# led2.net
KiCad netlist of a schematic drawn in Altium Designer
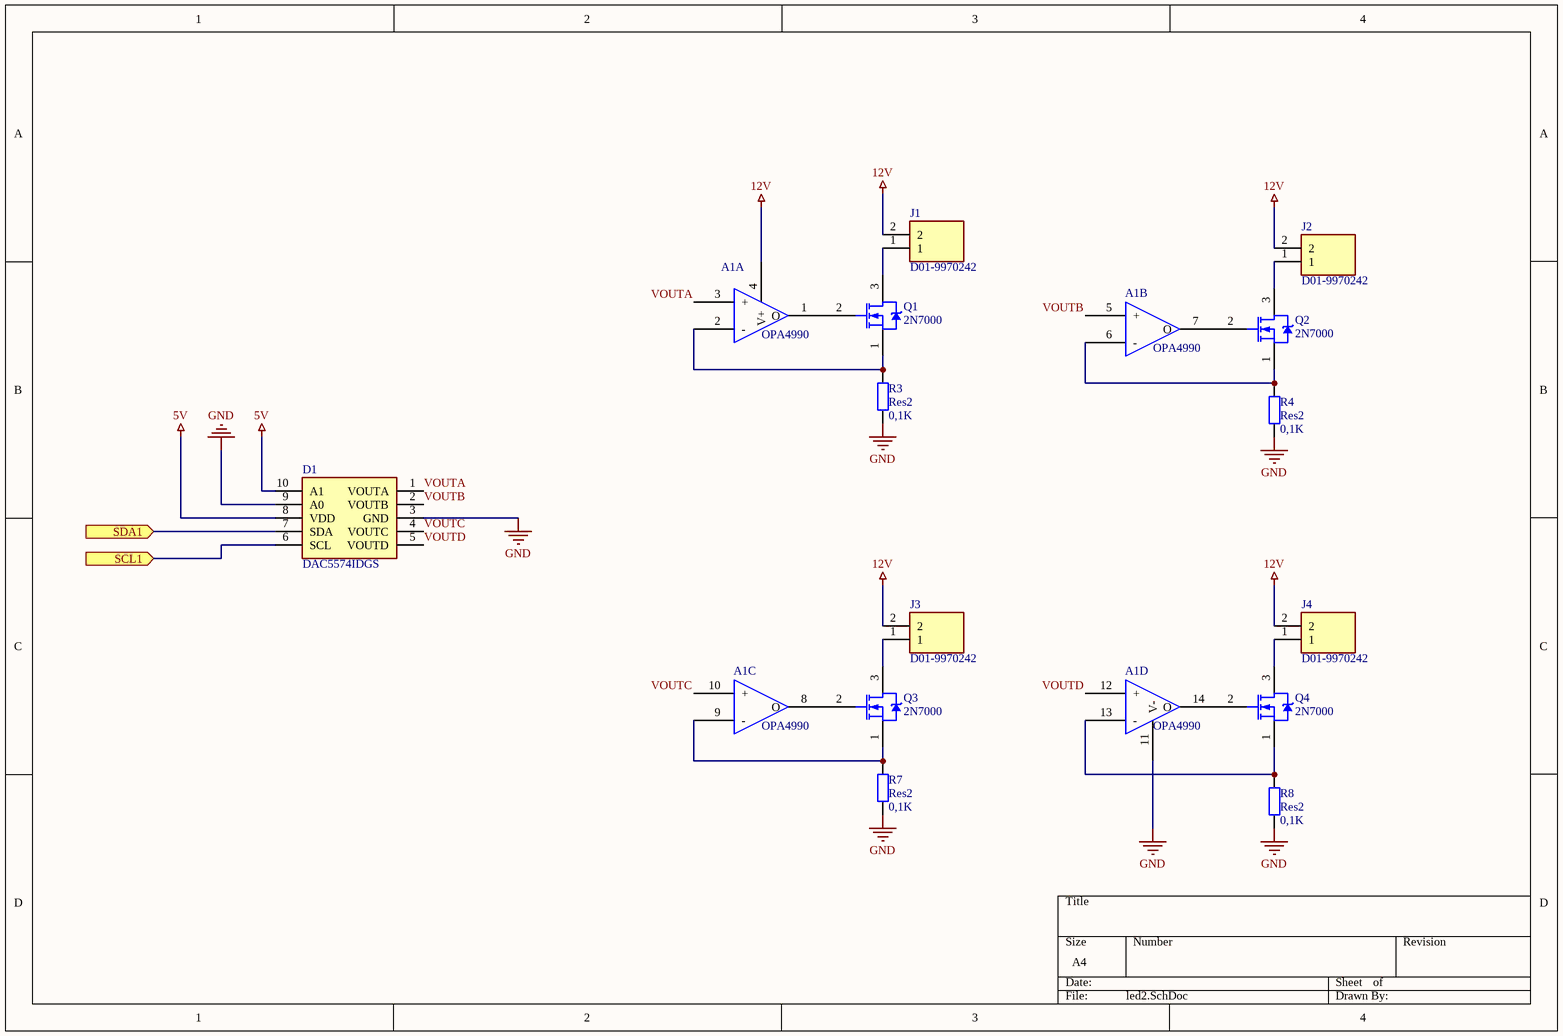
[diagram p0: led2.SchDoc]

(export (version "E")
  (design (tool "Eeschema 10.0.6"))
  (components
    (comp (ref "A1")
      (value "OPA4990")
      (footprint "SOIC127P600X175-14N")
      (libsource (lib "Kalibracija") (part "OPA4990"))
    )
    (comp (ref "D1")
      (value "DAC5574IDGS")
      (footprint "SOP50P490X110-10N")
      (description "Integrated Circuit")
      (fields
        (field (name "MOUSER PART NUMBER") "595-DAC5574IDGS")
        (field (name "RS PART NUMBER") "6621533P")
      )
      (libsource (lib "*") (part "DAC5574IDGS"))
    )
    (comp (ref "J1")
      (value "D01-9970242")
      (footprint "HDR1X2")
      (description "Connector")
      (fields (field (name "MOUSER PART NUMBER") "855-D01-9970242"))
      (libsource (lib "SamacSys2") (part "D01-9970242"))
    )
    (comp (ref "J2")
      (value "D01-9970242")
      (footprint "HDR1X2")
      (description "Connector")
      (fields (field (name "MOUSER PART NUMBER") "855-D01-9970242"))
      (libsource (lib "SamacSys2") (part "D01-9970242"))
    )
    (comp (ref "J3")
      (value "D01-9970242")
      (footprint "HDR1X2")
      (description "Connector")
      (fields (field (name "MOUSER PART NUMBER") "855-D01-9970242"))
      (libsource (lib "SamacSys2") (part "D01-9970242"))
    )
    (comp (ref "J4")
      (value "D01-9970242")
      (footprint "HDR1X2")
      (description "Connector")
      (fields (field (name "MOUSER PART NUMBER") "855-D01-9970242"))
      (libsource (lib "SamacSys2") (part "D01-9970242"))
    )
    (comp (ref "Q1")
      (value "2N7000")
      (footprint "ONSC-TO-92-3-29-11")
      (description "Small Signal MOSFET, 200 mA, 60 V, N-Channel, 3-Pin TO-92, Bulk Box")
      (fields (field (name "MANUFACTURER") "On Semiconductor"))
      (libsource (lib "Components - 24.04.20 - 07.58") (part "CMP-1058-00936-1"))
    )
    (comp (ref "Q2")
      (value "2N7000")
      (footprint "ONSC-TO-92-3-29-11")
      (description "Small Signal MOSFET, 200 mA, 60 V, N-Channel, 3-Pin TO-92, Bulk Box")
      (fields (field (name "MANUFACTURER") "On Semiconductor"))
      (libsource (lib "Components - 24.04.20 - 07.58") (part "CMP-1058-00936-1"))
    )
    (comp (ref "Q3")
      (value "2N7000")
      (footprint "ONSC-TO-92-3-29-11")
      (description "Small Signal MOSFET, 200 mA, 60 V, N-Channel, 3-Pin TO-92, Bulk Box")
      (fields (field (name "MANUFACTURER") "On Semiconductor"))
      (libsource (lib "Components - 24.04.20 - 07.58") (part "CMP-1058-00936-1"))
    )
    (comp (ref "Q4")
      (value "2N7000")
      (footprint "ONSC-TO-92-3-29-11")
      (description "Small Signal MOSFET, 200 mA, 60 V, N-Channel, 3-Pin TO-92, Bulk Box")
      (fields (field (name "MANUFACTURER") "On Semiconductor"))
      (libsource (lib "Components - 24.04.20 - 07.58") (part "CMP-1058-00936-1"))
    )
    (comp (ref "R3")
      (value "Res2")
      (footprint "C1210")
      (description "Resistor")
      (fields (field (name "ALTIUM_VALUE") "0,1K") (field (name "PUBLISHER") "Altium Limited"))
      (libsource (lib "Miscellaneous Devices") (part "Res2"))
    )
    (comp (ref "R4")
      (value "Res2")
      (footprint "C1210")
      (description "Resistor")
      (fields (field (name "ALTIUM_VALUE") "0,1K") (field (name "PUBLISHER") "Altium Limited"))
      (libsource (lib "Miscellaneous Devices") (part "Res2"))
    )
    (comp (ref "R7")
      (value "Res2")
      (footprint "C1210")
      (description "Resistor")
      (fields (field (name "ALTIUM_VALUE") "0,1K") (field (name "PUBLISHER") "Altium Limited"))
      (libsource (lib "Miscellaneous Devices") (part "Res2"))
    )
    (comp (ref "R8")
      (value "Res2")
      (footprint "C1210")
      (description "Resistor")
      (fields (field (name "ALTIUM_VALUE") "0,1K") (field (name "PUBLISHER") "Altium Limited"))
      (libsource (lib "Miscellaneous Devices") (part "Res2"))
    )
  )
  (nets
    (net (code "1") (name "/SCL1") (class "Default")
      (node (ref "D1") (pin "6") (pinfunction "SCL_6") (pintype "passive"))
    )
    (net (code "2") (name "/SDA1") (class "Default")
      (node (ref "D1") (pin "7") (pinfunction "SDA_7") (pintype "passive"))
    )
    (net (code "3") (name "/VOUTA") (class "Default")
      (node (ref "A1") (pin "3") (pinfunction "+_3") (pintype "passive"))
      (node (ref "D1") (pin "1") (pinfunction "VOUTA_1") (pintype "passive"))
    )
    (net (code "4") (name "/VOUTB") (class "Default")
      (node (ref "A1") (pin "5") (pinfunction "+_5") (pintype "passive"))
      (node (ref "D1") (pin "2") (pinfunction "VOUTB_2") (pintype "passive"))
    )
    (net (code "5") (name "/VOUTC") (class "Default")
      (node (ref "A1") (pin "10") (pinfunction "+_10") (pintype "passive"))
      (node (ref "D1") (pin "4") (pinfunction "VOUTC_4") (pintype "passive"))
    )
    (net (code "6") (name "/VOUTD") (class "Default")
      (node (ref "A1") (pin "12") (pinfunction "+_12") (pintype "passive"))
      (node (ref "D1") (pin "5") (pinfunction "VOUTD_5") (pintype "passive"))
    )
    (net (code "7") (name "5V") (class "Default")
      (node (ref "D1") (pin "10") (pinfunction "A1_10") (pintype "passive"))
      (node (ref "D1") (pin "8") (pinfunction "VDD_8") (pintype "passive"))
    )
    (net (code "8") (name "12V") (class "Default")
      (node (ref "A1") (pin "4") (pinfunction "V+_4") (pintype "power_in"))
      (node (ref "J1") (pin "2") (pinfunction "2_2") (pintype "passive"))
      (node (ref "J2") (pin "2") (pinfunction "2_2") (pintype "passive"))
      (node (ref "J3") (pin "2") (pinfunction "2_2") (pintype "passive"))
      (node (ref "J4") (pin "2") (pinfunction "2_2") (pintype "passive"))
    )
    (net (code "9") (name "GND") (class "Default")
      (node (ref "A1") (pin "11") (pinfunction "V-_11") (pintype "power_in"))
      (node (ref "D1") (pin "3") (pinfunction "GND_3") (pintype "passive"))
      (node (ref "D1") (pin "9") (pinfunction "A0_9") (pintype "passive"))
      (node (ref "R3") (pin "1") (pinfunction "1_1") (pintype "passive"))
      (node (ref "R4") (pin "1") (pinfunction "1_1") (pintype "passive"))
      (node (ref "R7") (pin "1") (pinfunction "1_1") (pintype "passive"))
      (node (ref "R8") (pin "1") (pinfunction "1_1") (pintype "passive"))
    )
    (net (code "10") (name "Net-(A1A--)") (class "Default")
      (node (ref "A1") (pin "2") (pinfunction "-_2") (pintype "passive"))
      (node (ref "Q1") (pin "1") (pinfunction "S_1") (pintype "passive"))
      (node (ref "R3") (pin "2") (pinfunction "2_2") (pintype "passive"))
    )
    (net (code "11") (name "Net-(A1A-O)") (class "Default")
      (node (ref "A1") (pin "1") (pinfunction "O_1") (pintype "passive"))
      (node (ref "Q1") (pin "2") (pinfunction "G_2") (pintype "passive"))
    )
    (net (code "12") (name "Net-(A1B--)") (class "Default")
      (node (ref "A1") (pin "6") (pinfunction "-_6") (pintype "passive"))
      (node (ref "Q2") (pin "1") (pinfunction "S_1") (pintype "passive"))
      (node (ref "R4") (pin "2") (pinfunction "2_2") (pintype "passive"))
    )
    (net (code "13") (name "Net-(A1B-O)") (class "Default")
      (node (ref "A1") (pin "7") (pinfunction "O_7") (pintype "passive"))
      (node (ref "Q2") (pin "2") (pinfunction "G_2") (pintype "passive"))
    )
    (net (code "14") (name "Net-(A1C--)") (class "Default")
      (node (ref "A1") (pin "9") (pinfunction "-_9") (pintype "passive"))
      (node (ref "Q3") (pin "1") (pinfunction "S_1") (pintype "passive"))
      (node (ref "R7") (pin "2") (pinfunction "2_2") (pintype "passive"))
    )
    (net (code "15") (name "Net-(A1C-O)") (class "Default")
      (node (ref "A1") (pin "8") (pinfunction "O_8") (pintype "passive"))
      (node (ref "Q3") (pin "2") (pinfunction "G_2") (pintype "passive"))
    )
    (net (code "16") (name "Net-(A1D--)") (class "Default")
      (node (ref "A1") (pin "13") (pinfunction "-_13") (pintype "passive"))
      (node (ref "Q4") (pin "1") (pinfunction "S_1") (pintype "passive"))
      (node (ref "R8") (pin "2") (pinfunction "2_2") (pintype "passive"))
    )
    (net (code "17") (name "Net-(A1D-O)") (class "Default")
      (node (ref "A1") (pin "14") (pinfunction "O_14") (pintype "passive"))
      (node (ref "Q4") (pin "2") (pinfunction "G_2") (pintype "passive"))
    )
    (net (code "18") (name "Net-(Q1-D)") (class "Default")
      (node (ref "J1") (pin "1") (pinfunction "1_1") (pintype "passive"))
      (node (ref "Q1") (pin "3") (pinfunction "D_3") (pintype "passive"))
    )
    (net (code "19") (name "Net-(Q2-D)") (class "Default")
      (node (ref "J2") (pin "1") (pinfunction "1_1") (pintype "passive"))
      (node (ref "Q2") (pin "3") (pinfunction "D_3") (pintype "passive"))
    )
    (net (code "20") (name "Net-(Q3-D)") (class "Default")
      (node (ref "J3") (pin "1") (pinfunction "1_1") (pintype "passive"))
      (node (ref "Q3") (pin "3") (pinfunction "D_3") (pintype "passive"))
    )
    (net (code "21") (name "Net-(Q4-D)") (class "Default")
      (node (ref "J4") (pin "1") (pinfunction "1_1") (pintype "passive"))
      (node (ref "Q4") (pin "3") (pinfunction "D_3") (pintype "passive"))
    )
  )
)
